# seven_seg_thermocouple_two.net
KiCad netlist of a schematic drawn in EAGLE
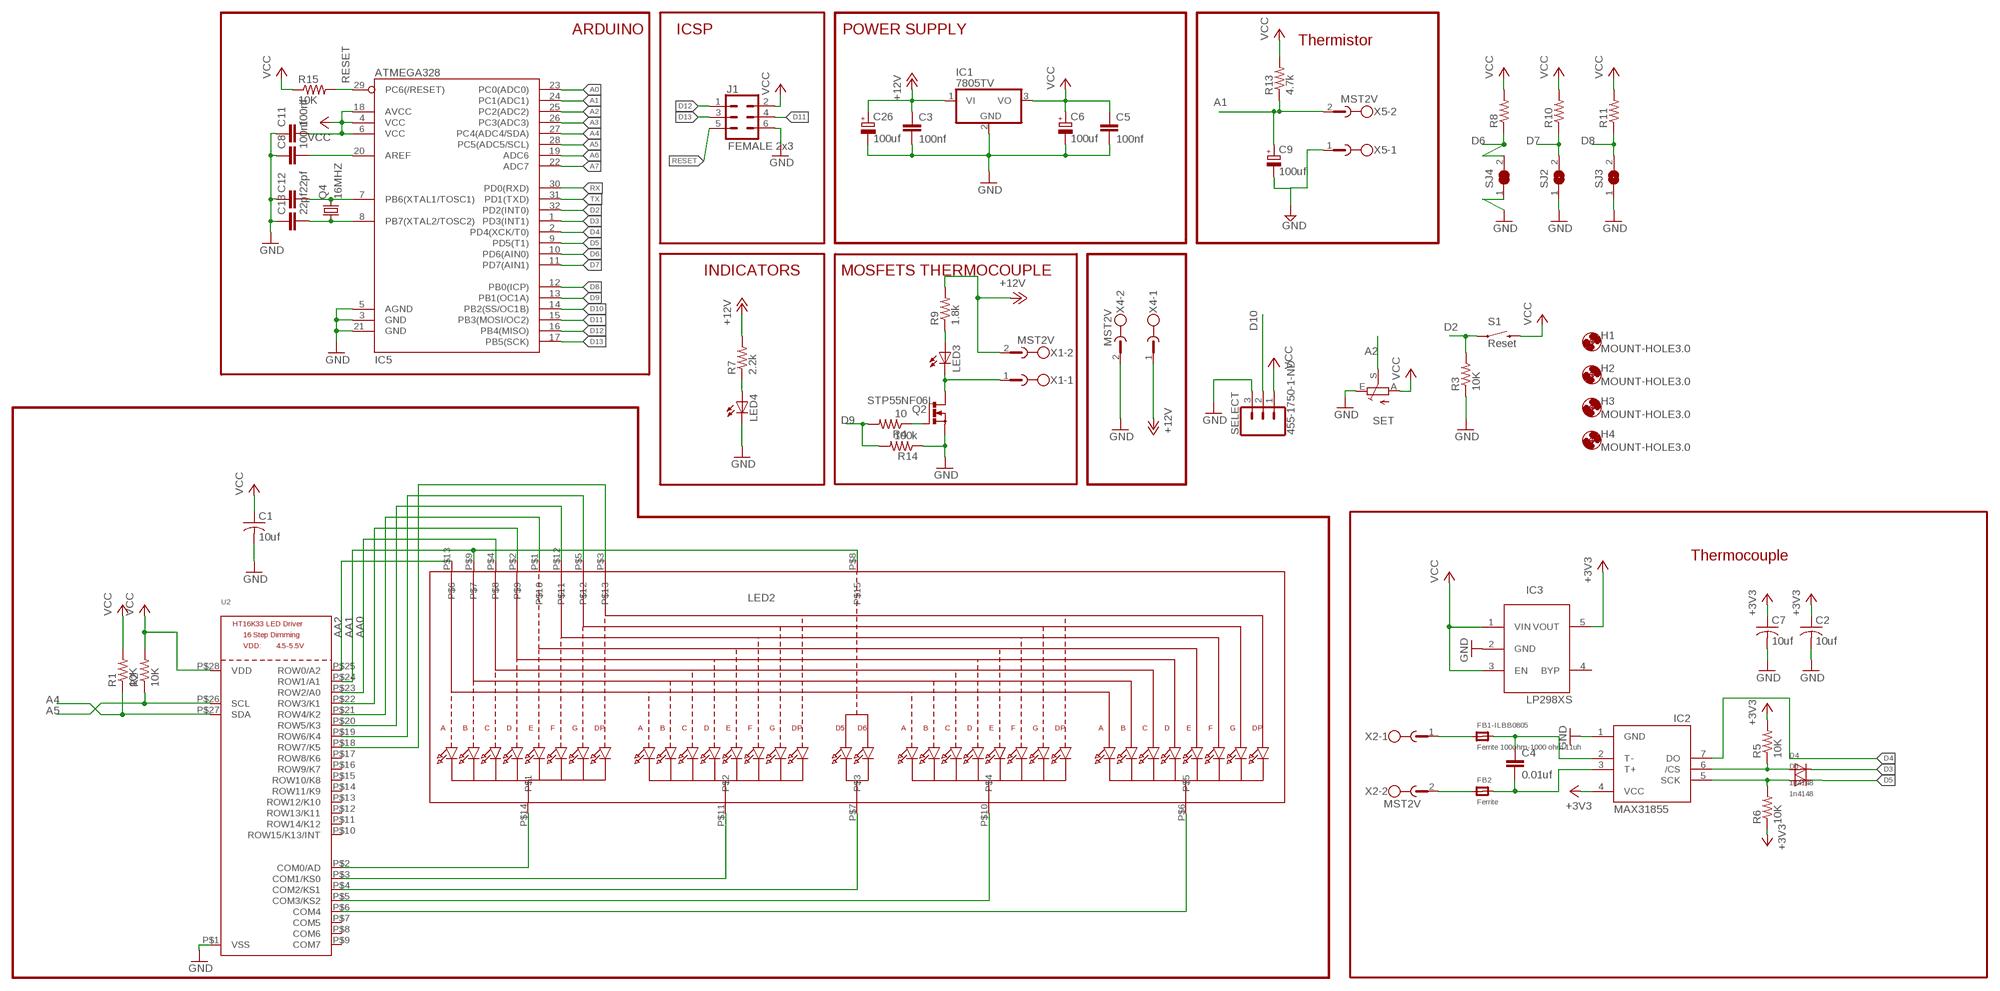
[diagram p0: schematic, sheet 1]

(export (version "E")
  (design (tool "Eeschema 10.0.6"))
  (components
    (comp (ref "C1")
      (value "10uf")
      (footprint "eagle-import:C1206")
      (libsource (lib "eagle-import") (part "C-USC1206"))
    )
    (comp (ref "C2")
      (value "10uf")
      (footprint "eagle-import:C1206")
      (libsource (lib "eagle-import") (part "C-USC1206"))
    )
    (comp (ref "C3")
      (value "100nf")
      (footprint "eagle-import:C1206")
      (libsource (lib "eagle-import") (part "C-EUC1206"))
    )
    (comp (ref "C4")
      (value "0.01uf")
      (footprint "eagle-import:C1206")
      (libsource (lib "eagle-import") (part "C-EUC1206"))
    )
    (comp (ref "C5")
      (value "100nf")
      (footprint "eagle-import:C1206")
      (libsource (lib "eagle-import") (part "C-EUC1206"))
    )
    (comp (ref "C6")
      (value "100uf")
      (footprint "eagle-import:PANASONIC_D")
      (libsource (lib "eagle-import") (part "CPOL-EUD"))
    )
    (comp (ref "C7")
      (value "10uf")
      (footprint "eagle-import:C1206")
      (libsource (lib "eagle-import") (part "C-USC1206"))
    )
    (comp (ref "C8")
      (value "100nf")
      (footprint "eagle-import:C1206")
      (libsource (lib "eagle-import") (part "C-EUC1206"))
    )
    (comp (ref "C9")
      (value "100uf")
      (footprint "eagle-import:PANASONIC_D")
      (libsource (lib "eagle-import") (part "CPOL-EUD"))
    )
    (comp (ref "C11")
      (value "100nf")
      (footprint "eagle-import:C1206")
      (libsource (lib "eagle-import") (part "C-EUC1206"))
    )
    (comp (ref "C12")
      (value "22pf")
      (footprint "eagle-import:C1206")
      (libsource (lib "eagle-import") (part "C-EUC1206"))
    )
    (comp (ref "C13")
      (value "22pf")
      (footprint "eagle-import:C1206")
      (libsource (lib "eagle-import") (part "C-EUC1206"))
    )
    (comp (ref "C26")
      (value "100uf")
      (footprint "eagle-import:PANASONIC_D")
      (libsource (lib "eagle-import") (part "CPOL-EUD"))
    )
    (comp (ref "D3")
      (value "1n4148")
      (footprint "eagle-import:SOD-123")
      (libsource (lib "eagle-import") (part "DIODESOD-123"))
    )
    (comp (ref "D4")
      (value "1n4148")
      (footprint "eagle-import:SOD-123")
      (libsource (lib "eagle-import") (part "DIODESOD-123"))
    )
    (comp (ref "FB1-ILBB0805")
      (value "Ferrite 100ohm-1000 ohm 11uh")
      (footprint "eagle-import:_0805")
      (libsource (lib "eagle-import") (part "FERRITE_0805"))
    )
    (comp (ref "FB2")
      (value "Ferrite")
      (footprint "eagle-import:_0805")
      (libsource (lib "eagle-import") (part "FERRITE_0805"))
    )
    (comp (ref "H1")
      (value "MOUNT-HOLE3.0")
      (footprint "eagle-import:3,0")
      (libsource (lib "eagle-import") (part "MOUNT-HOLE3.0"))
    )
    (comp (ref "H2")
      (value "MOUNT-HOLE3.0")
      (footprint "eagle-import:3,0")
      (libsource (lib "eagle-import") (part "MOUNT-HOLE3.0"))
    )
    (comp (ref "H3")
      (value "MOUNT-HOLE3.0")
      (footprint "eagle-import:3,0")
      (libsource (lib "eagle-import") (part "MOUNT-HOLE3.0"))
    )
    (comp (ref "H4")
      (value "MOUNT-HOLE3.0")
      (footprint "eagle-import:3,0")
      (libsource (lib "eagle-import") (part "MOUNT-HOLE3.0"))
    )
    (comp (ref "IC1")
      (value "7805TV")
      (footprint "eagle-import:TO220V")
      (libsource (lib "eagle-import") (part "78TV05"))
    )
    (comp (ref "IC2")
      (value "MAX31855")
      (footprint "eagle-import:SO08")
      (libsource (lib "eagle-import") (part "MAX6675"))
    )
    (comp (ref "IC3")
      (value "LP298XS")
      (footprint "eagle-import:SOT23-5L")
      (libsource (lib "eagle-import") (part "LP298XS"))
    )
    (comp (ref "IC5")
      (value "ATMEGA328")
      (footprint "eagle-import:TQFP32-08")
      (libsource (lib "eagle-import") (part "ATMEGA168"))
    )
    (comp (ref "J1")
      (value "FEMALE 2x3")
      (footprint "eagle-import:2X3")
      (libsource (lib "eagle-import") (part "CONN_03X2FEMALE"))
    )
    (comp (ref "LED2")
      (value "DISP_SEGMENT_4DIGIT_BL-Q56C43")
      (footprint "eagle-import:SEGMENT-BL-Q56C43")
      (libsource (lib "eagle-import") (part "DISP_SEGMENT_4DIGIT_BL-Q56C43"))
    )
    (comp (ref "LED3")
      (value "LEDCHIPLED_1206")
      (footprint "eagle-import:CHIPLED_1206")
      (libsource (lib "eagle-import") (part "LEDCHIPLED_1206"))
    )
    (comp (ref "LED4")
      (value "LEDCHIPLED_1206")
      (footprint "eagle-import:CHIPLED_1206")
      (libsource (lib "eagle-import") (part "LEDCHIPLED_1206"))
    )
    (comp (ref "Q2")
      (value "STP55NF06L")
      (footprint "eagle-import:TO220BV")
      (libsource (lib "eagle-import") (part "IRF512"))
    )
    (comp (ref "Q4")
      (value "16MHZ")
      (footprint "eagle-import:HC49_S")
      (libsource (lib "eagle-import") (part "CRYSTALHC49S"))
    )
    (comp (ref "R1")
      (value "10K")
      (footprint "eagle-import:R1206")
      (libsource (lib "eagle-import") (part "R-US_R1206"))
    )
    (comp (ref "R2")
      (value "10K")
      (footprint "eagle-import:R1206")
      (libsource (lib "eagle-import") (part "R-US_R1206"))
    )
    (comp (ref "R3")
      (value "10K")
      (footprint "eagle-import:R1206")
      (libsource (lib "eagle-import") (part "R-US_R1206"))
    )
    (comp (ref "R4")
      (value "10")
      (footprint "eagle-import:R1206")
      (libsource (lib "eagle-import") (part "R-US_R1206"))
    )
    (comp (ref "R5")
      (value "10K")
      (footprint "eagle-import:R1206")
      (libsource (lib "eagle-import") (part "R-US_R1206"))
    )
    (comp (ref "R6")
      (value "10K")
      (footprint "eagle-import:R1206")
      (libsource (lib "eagle-import") (part "R-US_R1206"))
    )
    (comp (ref "R7")
      (value "2.2k")
      (footprint "eagle-import:R1206")
      (libsource (lib "eagle-import") (part "R-US_R1206"))
    )
    (comp (ref "R8")
      (value "R-US_R1206")
      (footprint "eagle-import:R1206")
      (libsource (lib "eagle-import") (part "R-US_R1206"))
    )
    (comp (ref "R9")
      (value "1.8k")
      (footprint "eagle-import:R1206")
      (libsource (lib "eagle-import") (part "R-US_R1206"))
    )
    (comp (ref "R10")
      (value "R-US_R1206")
      (footprint "eagle-import:R1206")
      (libsource (lib "eagle-import") (part "R-US_R1206"))
    )
    (comp (ref "R11")
      (value "R-US_R1206")
      (footprint "eagle-import:R1206")
      (libsource (lib "eagle-import") (part "R-US_R1206"))
    )
    (comp (ref "R13")
      (value "4.7k")
      (footprint "eagle-import:R1206")
      (libsource (lib "eagle-import") (part "R-US_R1206"))
    )
    (comp (ref "R14")
      (value "100k")
      (footprint "eagle-import:R1206")
      (libsource (lib "eagle-import") (part "R-US_R1206"))
    )
    (comp (ref "R15")
      (value "10K")
      (footprint "eagle-import:R1206")
      (libsource (lib "eagle-import") (part "R-US_R1206"))
    )
    (comp (ref "S1")
      (value "Reset")
      (footprint "eagle-import:TACTILE-SWITCH-SMD-ALT01")
      (libsource (lib "eagle-import") (part "SWITCH-MOMENTARY-2SMD-ALT01"))
    )
    (comp (ref "SELECT")
      (value "455-1750-1-ND")
      (footprint "eagle-import:1X03")
      (libsource (lib "eagle-import") (part "CONN_03"))
    )
    (comp (ref "SET")
      (value "TRIM_EU-B25U")
      (footprint "eagle-import:B25U")
      (libsource (lib "eagle-import") (part "TRIM_EU-B25U"))
    )
    (comp (ref "SJ2") (value "SJ") (footprint "eagle-import:SJ") (libsource (lib "eagle-import") (part "SJ")))
    (comp (ref "SJ3") (value "SJ") (footprint "eagle-import:SJ") (libsource (lib "eagle-import") (part "SJ")))
    (comp (ref "SJ4")
      (value "SOLDERJUMPER_CLOSED")
      (footprint "eagle-import:SOLDERJUMPER_CLOSEDWIRE")
      (libsource (lib "eagle-import") (part "SOLDERJUMPER_CLOSED"))
    )
    (comp (ref "U2")
      (value "HT16K33_SOP28")
      (footprint "eagle-import:SOP28_300MIL")
      (libsource (lib "eagle-import") (part "HT16K33_SOP28"))
    )
    (comp (ref "X1")
      (value "MST2V")
      (footprint "eagle-import:MSTBV2")
      (libsource (lib "eagle-import") (part "MST2V"))
    )
    (comp (ref "X2")
      (value "MST2V")
      (footprint "eagle-import:MSTBV2")
      (libsource (lib "eagle-import") (part "MST2V"))
    )
    (comp (ref "X4")
      (value "MST2V")
      (footprint "eagle-import:MSTBV2")
      (libsource (lib "eagle-import") (part "MST2V"))
    )
    (comp (ref "X5")
      (value "MST2V")
      (footprint "eagle-import:MSTBV2")
      (libsource (lib "eagle-import") (part "MST2V"))
    )
  )
  (nets
    (net (code "1") (name "+3V3") (class "Default")
      (node (ref "C2") (pin "1") (pinfunction "1_1") (pintype "passive"))
      (node (ref "C7") (pin "1") (pinfunction "1_1") (pintype "passive"))
      (node (ref "IC2") (pin "4") (pinfunction "VCC_4") (pintype "power_in"))
      (node (ref "IC3") (pin "5") (pinfunction "VOUT_5") (pintype "bidirectional"))
      (node (ref "R5") (pin "2") (pinfunction "2_2") (pintype "passive"))
      (node (ref "R6") (pin "1") (pinfunction "1_1") (pintype "passive"))
    )
    (net (code "2") (name "+12V") (class "Default")
      (node (ref "C26") (pin "+") (pinfunction "+_+") (pintype "passive"))
      (node (ref "C3") (pin "1") (pinfunction "1_1") (pintype "passive"))
      (node (ref "IC1") (pin "1") (pinfunction "VI_1") (pintype "input"))
      (node (ref "R7") (pin "2") (pinfunction "2_2") (pintype "passive"))
      (node (ref "R9") (pin "2") (pinfunction "2_2") (pintype "passive"))
      (node (ref "X1") (pin "2") (pinfunction "1_2") (pintype "passive"))
      (node (ref "X4") (pin "1") (pinfunction "1_1") (pintype "passive"))
    )
    (net (code "3") (name "/AA0") (class "Default")
      (node (ref "LED2") (pin "P$4") (pinfunction "P$8_P$4") (pintype "bidirectional"))
      (node (ref "U2") (pin "P$23") (pinfunction "ROW2/A0_P$23") (pintype "bidirectional"))
    )
    (net (code "4") (name "/AA1") (class "Default")
      (node (ref "LED2") (pin "P$8") (pinfunction "P$15_P$8") (pintype "bidirectional"))
      (node (ref "LED2") (pin "P$9") (pinfunction "P$7_P$9") (pintype "bidirectional"))
      (node (ref "U2") (pin "P$24") (pinfunction "ROW1/A1_P$24") (pintype "bidirectional"))
    )
    (net (code "5") (name "/AA2") (class "Default")
      (node (ref "LED2") (pin "P$13") (pinfunction "P$6_P$13") (pintype "bidirectional"))
      (node (ref "U2") (pin "P$25") (pinfunction "ROW0/A2_P$25") (pintype "bidirectional"))
    )
    (net (code "6") (name "A0") (class "Default")
      (node (ref "IC5") (pin "23") (pinfunction "PC0(ADC0)_23") (pintype "bidirectional"))
    )
    (net (code "7") (name "A1") (class "Default")
      (node (ref "C9") (pin "+") (pinfunction "+_+") (pintype "passive"))
      (node (ref "IC5") (pin "24") (pinfunction "PC1(ADC1)_24") (pintype "bidirectional"))
      (node (ref "R13") (pin "1") (pinfunction "1_1") (pintype "passive"))
      (node (ref "X5") (pin "2") (pinfunction "1_2") (pintype "passive"))
    )
    (net (code "8") (name "A2") (class "Default")
      (node (ref "IC5") (pin "25") (pinfunction "PC2(ADC2)_25") (pintype "bidirectional"))
      (node (ref "SET") (pin "S") (pinfunction "S_S") (pintype "passive"))
    )
    (net (code "9") (name "A3") (class "Default")
      (node (ref "IC5") (pin "26") (pinfunction "PC3(ADC3)_26") (pintype "bidirectional"))
    )
    (net (code "10") (name "A4") (class "Default")
      (node (ref "IC5") (pin "27") (pinfunction "PC4(ADC4/SDA)_27") (pintype "bidirectional"))
      (node (ref "R1") (pin "1") (pinfunction "1_1") (pintype "passive"))
      (node (ref "U2") (pin "P$27") (pinfunction "SDA_P$27") (pintype "bidirectional"))
    )
    (net (code "11") (name "A5") (class "Default")
      (node (ref "IC5") (pin "28") (pinfunction "PC5(ADC5/SCL)_28") (pintype "bidirectional"))
      (node (ref "R2") (pin "1") (pinfunction "1_1") (pintype "passive"))
      (node (ref "U2") (pin "P$26") (pinfunction "SCL_P$26") (pintype "bidirectional"))
    )
    (net (code "12") (name "A6") (class "Default")
      (node (ref "IC5") (pin "19") (pinfunction "ADC6_19") (pintype "bidirectional"))
    )
    (net (code "13") (name "A7") (class "Default")
      (node (ref "IC5") (pin "22") (pinfunction "ADC7_22") (pintype "bidirectional"))
    )
    (net (code "14") (name "D2") (class "Default")
      (node (ref "IC5") (pin "32") (pinfunction "PD2(INT0)_32") (pintype "bidirectional"))
      (node (ref "R3") (pin "2") (pinfunction "2_2") (pintype "passive"))
      (node (ref "S1") (pin "1") (pinfunction "1_1") (pintype "passive"))
      (node (ref "S1") (pin "2") (pinfunction "1_2") (pintype "passive"))
    )
    (net (code "15") (name "D3") (class "Default")
      (node (ref "D4") (pin "C") (pinfunction "C_C") (pintype "passive"))
      (node (ref "IC5") (pin "1") (pinfunction "PD3(INT1)_1") (pintype "bidirectional"))
    )
    (net (code "16") (name "D4") (class "Default")
      (node (ref "IC2") (pin "7") (pinfunction "DO_7") (pintype "output"))
      (node (ref "IC5") (pin "2") (pinfunction "PD4(XCK/T0)_2") (pintype "bidirectional"))
    )
    (net (code "17") (name "D5") (class "Default")
      (node (ref "D3") (pin "C") (pinfunction "C_C") (pintype "passive"))
      (node (ref "IC5") (pin "9") (pinfunction "PD5(T1)_9") (pintype "bidirectional"))
    )
    (net (code "18") (name "D6") (class "Default")
      (node (ref "IC5") (pin "10") (pinfunction "PD6(AIN0)_10") (pintype "bidirectional"))
      (node (ref "R8") (pin "1") (pinfunction "1_1") (pintype "passive"))
      (node (ref "SJ4") (pin "2") (pinfunction "2_2") (pintype "passive"))
    )
    (net (code "19") (name "D7") (class "Default")
      (node (ref "IC5") (pin "11") (pinfunction "PD7(AIN1)_11") (pintype "bidirectional"))
      (node (ref "R10") (pin "1") (pinfunction "1_1") (pintype "passive"))
      (node (ref "SJ2") (pin "2") (pinfunction "2_2") (pintype "passive"))
    )
    (net (code "20") (name "D8") (class "Default")
      (node (ref "IC5") (pin "12") (pinfunction "PB0(ICP)_12") (pintype "bidirectional"))
      (node (ref "R11") (pin "1") (pinfunction "1_1") (pintype "passive"))
      (node (ref "SJ3") (pin "2") (pinfunction "2_2") (pintype "passive"))
    )
    (net (code "21") (name "D9") (class "Default")
      (node (ref "IC5") (pin "13") (pinfunction "PB1(OC1A)_13") (pintype "bidirectional"))
      (node (ref "R14") (pin "2") (pinfunction "2_2") (pintype "passive"))
      (node (ref "R4") (pin "2") (pinfunction "2_2") (pintype "passive"))
    )
    (net (code "22") (name "D10") (class "Default")
      (node (ref "IC5") (pin "14") (pinfunction "PB2(SS/OC1B)_14") (pintype "bidirectional"))
      (node (ref "SELECT") (pin "2") (pinfunction "2_2") (pintype "passive"))
    )
    (net (code "23") (name "D11") (class "Default")
      (node (ref "IC5") (pin "15") (pinfunction "PB3(MOSI/OC2)_15") (pintype "bidirectional"))
      (node (ref "J1") (pin "4") (pinfunction "4_4") (pintype "bidirectional"))
    )
    (net (code "24") (name "D12") (class "Default")
      (node (ref "IC5") (pin "16") (pinfunction "PB4(MISO)_16") (pintype "bidirectional"))
      (node (ref "J1") (pin "1") (pinfunction "1_1") (pintype "bidirectional"))
    )
    (net (code "25") (name "D13") (class "Default")
      (node (ref "IC5") (pin "17") (pinfunction "PB5(SCK)_17") (pintype "bidirectional"))
      (node (ref "J1") (pin "3") (pinfunction "3_3") (pintype "bidirectional"))
    )
    (net (code "26") (name "GND") (class "Default")
      (node (ref "C1") (pin "2") (pinfunction "2_2") (pintype "passive"))
      (node (ref "C11") (pin "1") (pinfunction "1_1") (pintype "passive"))
      (node (ref "C12") (pin "1") (pinfunction "1_1") (pintype "passive"))
      (node (ref "C13") (pin "1") (pinfunction "1_1") (pintype "passive"))
      (node (ref "C2") (pin "2") (pinfunction "2_2") (pintype "passive"))
      (node (ref "C26") (pin "-") (pinfunction "-_-") (pintype "passive"))
      (node (ref "C3") (pin "2") (pinfunction "2_2") (pintype "passive"))
      (node (ref "C5") (pin "2") (pinfunction "2_2") (pintype "passive"))
      (node (ref "C6") (pin "-") (pinfunction "-_-") (pintype "passive"))
      (node (ref "C7") (pin "2") (pinfunction "2_2") (pintype "passive"))
      (node (ref "C8") (pin "1") (pinfunction "1_1") (pintype "passive"))
      (node (ref "C9") (pin "-") (pinfunction "-_-") (pintype "passive"))
      (node (ref "IC1") (pin "2") (pinfunction "GND_2") (pintype "passive"))
      (node (ref "IC2") (pin "1") (pinfunction "GND_1") (pintype "power_in"))
      (node (ref "IC3") (pin "2") (pinfunction "GND_2") (pintype "bidirectional"))
      (node (ref "IC5") (pin "21") (pinfunction "GND_21") (pintype "bidirectional"))
      (node (ref "IC5") (pin "3") (pinfunction "GND_3") (pintype "bidirectional"))
      (node (ref "IC5") (pin "5") (pinfunction "AGND_5") (pintype "bidirectional"))
      (node (ref "J1") (pin "6") (pinfunction "6_6") (pintype "bidirectional"))
      (node (ref "LED4") (pin "C") (pinfunction "C_C") (pintype "passive"))
      (node (ref "Q2") (pin "S") (pinfunction "S_S") (pintype "passive"))
      (node (ref "R14") (pin "1") (pinfunction "1_1") (pintype "passive"))
      (node (ref "R3") (pin "1") (pinfunction "1_1") (pintype "passive"))
      (node (ref "SELECT") (pin "3") (pinfunction "3_3") (pintype "passive"))
      (node (ref "SET") (pin "E") (pinfunction "E_E") (pintype "passive"))
      (node (ref "SJ2") (pin "1") (pinfunction "1_1") (pintype "passive"))
      (node (ref "SJ3") (pin "1") (pinfunction "1_1") (pintype "passive"))
      (node (ref "SJ4") (pin "1") (pinfunction "1_1") (pintype "passive"))
      (node (ref "U2") (pin "P$1") (pinfunction "VSS_P$1") (pintype "bidirectional"))
      (node (ref "X4") (pin "2") (pinfunction "1_2") (pintype "passive"))
      (node (ref "X5") (pin "1") (pinfunction "1_1") (pintype "passive"))
    )
    (net (code "27") (name "Net-(FB1-ILBB0805-P$1)") (class "Default")
      (node (ref "FB1-ILBB0805") (pin "1") (pinfunction "P$1_1") (pintype "passive"))
      (node (ref "X2") (pin "1") (pinfunction "1_1") (pintype "passive"))
    )
    (net (code "28") (name "Net-(FB1-ILBB0805-P$2)") (class "Default")
      (node (ref "C4") (pin "1") (pinfunction "1_1") (pintype "passive"))
      (node (ref "FB1-ILBB0805") (pin "2") (pinfunction "P$2_2") (pintype "passive"))
      (node (ref "IC2") (pin "2") (pinfunction "T-_2") (pintype "input"))
    )
    (net (code "29") (name "Net-(FB2-P$1)") (class "Default")
      (node (ref "FB2") (pin "1") (pinfunction "P$1_1") (pintype "passive"))
      (node (ref "X2") (pin "2") (pinfunction "1_2") (pintype "passive"))
    )
    (net (code "30") (name "Net-(FB2-P$2)") (class "Default")
      (node (ref "C4") (pin "2") (pinfunction "2_2") (pintype "passive"))
      (node (ref "FB2") (pin "2") (pinfunction "P$2_2") (pintype "passive"))
      (node (ref "IC2") (pin "3") (pinfunction "T+_3") (pintype "input"))
    )
    (net (code "31") (name "Net-(IC2-SCK)") (class "Default")
      (node (ref "D3") (pin "A") (pinfunction "A_A") (pintype "passive"))
      (node (ref "IC2") (pin "5") (pinfunction "SCK_5") (pintype "input"))
      (node (ref "R6") (pin "2") (pinfunction "2_2") (pintype "passive"))
    )
    (net (code "32") (name "Net-(IC2-{slash}CS)") (class "Default")
      (node (ref "D4") (pin "A") (pinfunction "A_A") (pintype "passive"))
      (node (ref "IC2") (pin "6") (pinfunction "/CS_6") (pintype "input"))
      (node (ref "R5") (pin "1") (pinfunction "1_1") (pintype "passive"))
    )
    (net (code "33") (name "Net-(IC5-AREF)") (class "Default")
      (node (ref "C8") (pin "2") (pinfunction "2_2") (pintype "passive"))
      (node (ref "IC5") (pin "20") (pinfunction "AREF_20") (pintype "bidirectional"))
    )
    (net (code "34") (name "Net-(IC5-PB6(XTAL1{slash}TOSC1))") (class "Default")
      (node (ref "C12") (pin "2") (pinfunction "2_2") (pintype "passive"))
      (node (ref "IC5") (pin "7") (pinfunction "PB6(XTAL1/TOSC1)_7") (pintype "bidirectional"))
      (node (ref "Q4") (pin "2") (pinfunction "2_2") (pintype "passive"))
    )
    (net (code "35") (name "Net-(IC5-PB7(XTAL2{slash}TOSC2))") (class "Default")
      (node (ref "C13") (pin "2") (pinfunction "2_2") (pintype "passive"))
      (node (ref "IC5") (pin "8") (pinfunction "PB7(XTAL2/TOSC2)_8") (pintype "bidirectional"))
      (node (ref "Q4") (pin "1") (pinfunction "1_1") (pintype "passive"))
    )
    (net (code "36") (name "Net-(LED2-P$1)") (class "Default")
      (node (ref "LED2") (pin "P$14") (pinfunction "P$1_P$14") (pintype "bidirectional"))
      (node (ref "U2") (pin "P$2") (pinfunction "COM0/AD_P$2") (pintype "bidirectional"))
    )
    (net (code "37") (name "Net-(LED2-P$2)") (class "Default")
      (node (ref "LED2") (pin "P$11") (pinfunction "P$2_P$11") (pintype "bidirectional"))
      (node (ref "U2") (pin "P$3") (pinfunction "COM1/KS0_P$3") (pintype "bidirectional"))
    )
    (net (code "38") (name "Net-(LED2-P$3)") (class "Default")
      (node (ref "LED2") (pin "P$7") (pinfunction "P$3_P$7") (pintype "bidirectional"))
      (node (ref "U2") (pin "P$4") (pinfunction "COM2/KS1_P$4") (pintype "bidirectional"))
    )
    (net (code "39") (name "Net-(LED2-P$4)") (class "Default")
      (node (ref "LED2") (pin "P$10") (pinfunction "P$4_P$10") (pintype "bidirectional"))
      (node (ref "U2") (pin "P$5") (pinfunction "COM3/KS2_P$5") (pintype "bidirectional"))
    )
    (net (code "40") (name "Net-(LED2-P$5)") (class "Default")
      (node (ref "LED2") (pin "P$6") (pinfunction "P$5_P$6") (pintype "bidirectional"))
      (node (ref "U2") (pin "P$6") (pinfunction "COM4_P$6") (pintype "bidirectional"))
    )
    (net (code "41") (name "Net-(LED2-P$9)") (class "Default")
      (node (ref "LED2") (pin "P$2") (pinfunction "P$9_P$2") (pintype "bidirectional"))
      (node (ref "U2") (pin "P$22") (pinfunction "ROW3/K1_P$22") (pintype "bidirectional"))
    )
    (net (code "42") (name "Net-(LED2-P$10)") (class "Default")
      (node (ref "LED2") (pin "P$1") (pinfunction "P$10_P$1") (pintype "bidirectional"))
      (node (ref "U2") (pin "P$21") (pinfunction "ROW4/K2_P$21") (pintype "bidirectional"))
    )
    (net (code "43") (name "Net-(LED2-P$11)") (class "Default")
      (node (ref "LED2") (pin "P$12") (pinfunction "P$11_P$12") (pintype "bidirectional"))
      (node (ref "U2") (pin "P$20") (pinfunction "ROW5/K3_P$20") (pintype "bidirectional"))
    )
    (net (code "44") (name "Net-(LED2-P$12)") (class "Default")
      (node (ref "LED2") (pin "P$5") (pinfunction "P$12_P$5") (pintype "bidirectional"))
      (node (ref "U2") (pin "P$19") (pinfunction "ROW6/K4_P$19") (pintype "bidirectional"))
    )
    (net (code "45") (name "Net-(LED2-P$13)") (class "Default")
      (node (ref "LED2") (pin "P$3") (pinfunction "P$13_P$3") (pintype "bidirectional"))
      (node (ref "U2") (pin "P$18") (pinfunction "ROW7/K5_P$18") (pintype "bidirectional"))
    )
    (net (code "46") (name "Net-(LED3-PadA)") (class "Default")
      (node (ref "LED3") (pin "A") (pinfunction "A_A") (pintype "passive"))
      (node (ref "R9") (pin "1") (pinfunction "1_1") (pintype "passive"))
    )
    (net (code "47") (name "Net-(LED3-PadC)") (class "Default")
      (node (ref "LED3") (pin "C") (pinfunction "C_C") (pintype "passive"))
      (node (ref "Q2") (pin "D") (pinfunction "D_D") (pintype "passive"))
      (node (ref "X1") (pin "1") (pinfunction "1_1") (pintype "passive"))
    )
    (net (code "48") (name "Net-(LED4-PadA)") (class "Default")
      (node (ref "LED4") (pin "A") (pinfunction "A_A") (pintype "passive"))
      (node (ref "R7") (pin "1") (pinfunction "1_1") (pintype "passive"))
    )
    (net (code "49") (name "Net-(Q2-PadG)") (class "Default")
      (node (ref "Q2") (pin "G") (pinfunction "G_G") (pintype "passive"))
      (node (ref "R4") (pin "1") (pinfunction "1_1") (pintype "passive"))
    )
    (net (code "50") (name "RESET") (class "Default")
      (node (ref "IC5") (pin "29") (pinfunction "PC6(/RESET)_29") (pintype "bidirectional"))
      (node (ref "J1") (pin "5") (pinfunction "5_5") (pintype "bidirectional"))
      (node (ref "R15") (pin "2") (pinfunction "2_2") (pintype "passive"))
    )
    (net (code "51") (name "RX") (class "Default")
      (node (ref "IC5") (pin "30") (pinfunction "PD0(RXD)_30") (pintype "bidirectional"))
    )
    (net (code "52") (name "TX") (class "Default")
      (node (ref "IC5") (pin "31") (pinfunction "PD1(TXD)_31") (pintype "bidirectional"))
    )
    (net (code "53") (name "VCC") (class "Default")
      (node (ref "C1") (pin "1") (pinfunction "1_1") (pintype "passive"))
      (node (ref "C11") (pin "2") (pinfunction "2_2") (pintype "passive"))
      (node (ref "C5") (pin "1") (pinfunction "1_1") (pintype "passive"))
      (node (ref "C6") (pin "+") (pinfunction "+_+") (pintype "passive"))
      (node (ref "IC1") (pin "3") (pinfunction "VO_3") (pintype "passive"))
      (node (ref "IC3") (pin "1") (pinfunction "VIN_1") (pintype "bidirectional"))
      (node (ref "IC3") (pin "3") (pinfunction "EN_3") (pintype "bidirectional"))
      (node (ref "IC5") (pin "18") (pinfunction "AVCC_18") (pintype "bidirectional"))
      (node (ref "IC5") (pin "4") (pinfunction "VCC_4") (pintype "bidirectional"))
      (node (ref "IC5") (pin "6") (pinfunction "VCC_6") (pintype "bidirectional"))
      (node (ref "J1") (pin "2") (pinfunction "2_2") (pintype "bidirectional"))
      (node (ref "R1") (pin "2") (pinfunction "2_2") (pintype "passive"))
      (node (ref "R10") (pin "2") (pinfunction "2_2") (pintype "passive"))
      (node (ref "R11") (pin "2") (pinfunction "2_2") (pintype "passive"))
      (node (ref "R13") (pin "2") (pinfunction "2_2") (pintype "passive"))
      (node (ref "R15") (pin "1") (pinfunction "1_1") (pintype "passive"))
      (node (ref "R2") (pin "2") (pinfunction "2_2") (pintype "passive"))
      (node (ref "R8") (pin "2") (pinfunction "2_2") (pintype "passive"))
      (node (ref "S1") (pin "3") (pinfunction "2_3") (pintype "passive"))
      (node (ref "S1") (pin "4") (pinfunction "2_4") (pintype "passive"))
      (node (ref "SELECT") (pin "1") (pinfunction "1_1") (pintype "passive"))
      (node (ref "SET") (pin "A") (pinfunction "A_A") (pintype "passive"))
      (node (ref "U2") (pin "P$28") (pinfunction "VDD_P$28") (pintype "bidirectional"))
    )
    (net (code "54") (name "unconnected-(IC3-BYP-Pad4)") (class "Default")
      (node (ref "IC3") (pin "4") (pinfunction "BYP_4") (pintype "bidirectional"))
    )
    (net (code "55") (name "unconnected-(U2-COM5-PadP$7)") (class "Default")
      (node (ref "U2") (pin "P$7") (pinfunction "COM5_P$7") (pintype "bidirectional"))
    )
    (net (code "56") (name "unconnected-(U2-COM6-PadP$8)") (class "Default")
      (node (ref "U2") (pin "P$8") (pinfunction "COM6_P$8") (pintype "bidirectional"))
    )
    (net (code "57") (name "unconnected-(U2-COM7-PadP$9)") (class "Default")
      (node (ref "U2") (pin "P$9") (pinfunction "COM7_P$9") (pintype "bidirectional"))
    )
    (net (code "58") (name "unconnected-(U2-ROW8{slash}K6-PadP$17)") (class "Default")
      (node (ref "U2") (pin "P$17") (pinfunction "ROW8/K6_P$17") (pintype "bidirectional"))
    )
    (net (code "59") (name "unconnected-(U2-ROW9{slash}K7-PadP$16)") (class "Default")
      (node (ref "U2") (pin "P$16") (pinfunction "ROW9/K7_P$16") (pintype "bidirectional"))
    )
    (net (code "60") (name "unconnected-(U2-ROW10{slash}K8-PadP$15)") (class "Default")
      (node (ref "U2") (pin "P$15") (pinfunction "ROW10/K8_P$15") (pintype "bidirectional"))
    )
    (net (code "61") (name "unconnected-(U2-ROW11{slash}K9-PadP$14)") (class "Default")
      (node (ref "U2") (pin "P$14") (pinfunction "ROW11/K9_P$14") (pintype "bidirectional"))
    )
    (net (code "62") (name "unconnected-(U2-ROW12{slash}K10-PadP$13)") (class "Default")
      (node (ref "U2") (pin "P$13") (pinfunction "ROW12/K10_P$13") (pintype "bidirectional"))
    )
    (net (code "63") (name "unconnected-(U2-ROW13{slash}K11-PadP$12)") (class "Default")
      (node (ref "U2") (pin "P$12") (pinfunction "ROW13/K11_P$12") (pintype "bidirectional"))
    )
    (net (code "64") (name "unconnected-(U2-ROW14{slash}K12-PadP$11)") (class "Default")
      (node (ref "U2") (pin "P$11") (pinfunction "ROW14/K12_P$11") (pintype "bidirectional"))
    )
    (net (code "65") (name "unconnected-(U2-ROW15{slash}K13{slash}INT-PadP$10)") (class "Default")
      (node (ref "U2") (pin "P$10") (pinfunction "ROW15/K13/INT_P$10") (pintype "bidirectional"))
    )
  )
)
